# Sheet1.net
KiCad netlist of a schematic drawn in Altium Designer
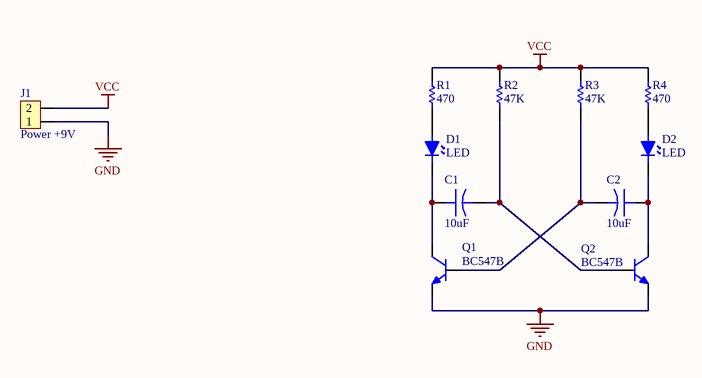
[diagram p0: Sheet1.SchDoc]

(export (version "E")
  (design (tool "Eeschema 10.0.6"))
  (components
    (comp (ref "C1")
      (value "10uF")
      (footprint "C-EL_5x11x2mm")
      (description "CAPACITOR ELECTROLYTIC")
      (libsource (lib "IOElectro") (part "CAP-EL"))
    )
    (comp (ref "C2")
      (value "10uF")
      (footprint "C-EL_5x11x2mm")
      (description "CAPACITOR ELECTROLYTIC")
      (libsource (lib "IOElectro") (part "CAP-EL"))
    )
    (comp (ref "D1") (value "LED") (footprint "LED-3MM") (libsource (lib "IOElectro") (part "LED")))
    (comp (ref "D2") (value "LED") (footprint "LED-3MM") (libsource (lib "IOElectro") (part "LED")))
    (comp (ref "J1")
      (value "Power +9V")
      (footprint "PH-1X2-N3D")
      (description "PIN HEADER 1x2 2.56mm")
      (libsource (lib "IOElectro") (part "PH-1X2"))
    )
    (comp (ref "Q1")
      (value "BC547B")
      (footprint "TO-92")
      (description "NPN TRANSISTOR 1.5A 40V SOT-23 R")
      (fields (field (name "MANUFACTURER") "ON Semiconductor / Fairchild") (field (name "VOLTAGE") "40V"))
      (libsource (lib "IOElectro") (part "BC547B"))
    )
    (comp (ref "Q2")
      (value "BC547B")
      (footprint "TO-92")
      (description "NPN TRANSISTOR 1.5A 40V SOT-23 R")
      (fields (field (name "MANUFACTURER") "ON Semiconductor / Fairchild") (field (name "VOLTAGE") "40V"))
      (libsource (lib "IOElectro") (part "BC547B"))
    )
    (comp (ref "R1") (value "470") (footprint "R-1/4W-DIP") (libsource (lib "IOElectro") (part "RES")))
    (comp (ref "R2") (value "47K") (footprint "R-1/4W-DIP") (libsource (lib "IOElectro") (part "RES")))
    (comp (ref "R3") (value "47K") (footprint "R-1/4W-DIP") (libsource (lib "IOElectro") (part "RES")))
    (comp (ref "R4") (value "470") (footprint "R-1/4W-DIP") (libsource (lib "IOElectro") (part "RES")))
  )
  (nets
    (net (code "1") (name "GND") (class "Default")
      (node (ref "J1") (pin "1") (pinfunction "1_1") (pintype "passive"))
      (node (ref "Q1") (pin "3") (pinfunction "E_3") (pintype "passive"))
      (node (ref "Q2") (pin "3") (pinfunction "E_3") (pintype "passive"))
    )
    (net (code "2") (name "Net-(D1-PadA)") (class "Default")
      (node (ref "D1") (pin "A") (pinfunction "A_A") (pintype "passive"))
      (node (ref "R1") (pin "1") (pinfunction "1_1") (pintype "passive"))
    )
    (net (code "3") (name "Net-(D2-PadA)") (class "Default")
      (node (ref "D2") (pin "A") (pinfunction "A_A") (pintype "passive"))
      (node (ref "R4") (pin "1") (pinfunction "1_1") (pintype "passive"))
    )
    (net (code "4") (name "Net-(Q1-B)") (class "Default")
      (node (ref "C2") (pin "K") (pinfunction "K_K") (pintype "passive"))
      (node (ref "Q1") (pin "2") (pinfunction "B_2") (pintype "passive"))
      (node (ref "R3") (pin "1") (pinfunction "1_1") (pintype "passive"))
    )
    (net (code "5") (name "Net-(Q1-C)") (class "Default")
      (node (ref "C1") (pin "A") (pinfunction "A_A") (pintype "passive"))
      (node (ref "D1") (pin "K") (pinfunction "K_K") (pintype "passive"))
      (node (ref "Q1") (pin "1") (pinfunction "C_1") (pintype "passive"))
    )
    (net (code "6") (name "Net-(Q2-B)") (class "Default")
      (node (ref "C1") (pin "K") (pinfunction "K_K") (pintype "passive"))
      (node (ref "Q2") (pin "2") (pinfunction "B_2") (pintype "passive"))
      (node (ref "R2") (pin "1") (pinfunction "1_1") (pintype "passive"))
    )
    (net (code "7") (name "Net-(Q2-C)") (class "Default")
      (node (ref "C2") (pin "A") (pinfunction "A_A") (pintype "passive"))
      (node (ref "D2") (pin "K") (pinfunction "K_K") (pintype "passive"))
      (node (ref "Q2") (pin "1") (pinfunction "C_1") (pintype "passive"))
    )
    (net (code "8") (name "VCC") (class "Default")
      (node (ref "J1") (pin "2") (pinfunction "2_2") (pintype "passive"))
      (node (ref "R1") (pin "2") (pinfunction "2_2") (pintype "passive"))
      (node (ref "R2") (pin "2") (pinfunction "2_2") (pintype "passive"))
      (node (ref "R3") (pin "2") (pinfunction "2_2") (pintype "passive"))
      (node (ref "R4") (pin "2") (pinfunction "2_2") (pintype "passive"))
    )
  )
)
